# Schematic-Indheater_Altium.net
KiCad netlist of a schematic drawn in Altium Designer
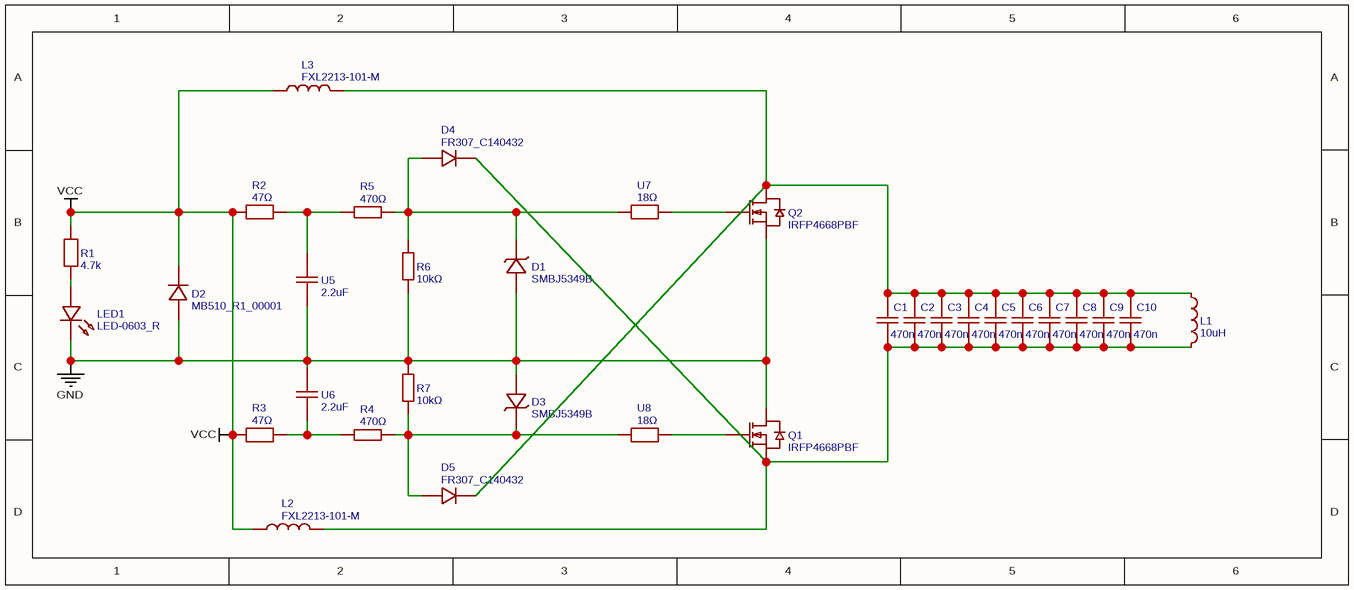
[diagram p0: Schematic-Indheater (Altium).schdoc]

(export (version "E")
  (design (tool "Eeschema 10.0.6"))
  (components
    (comp (ref "C1")
      (value "470n")
      (fields
        (field (name "MANUFACTURER") "faratronic(厦门法拉)")
        (field (name "MANUFACTURER PART") "C222J474K60C000")
        (field (name "CONTRIBUTOR") "LCSC")
      )
      (libsource (lib "altium-import") (part "root_1_470n_"))
    )
    (comp (ref "C2")
      (value "470n")
      (fields
        (field (name "MANUFACTURER") "faratronic(厦门法拉)")
        (field (name "MANUFACTURER PART") "C222J474K60C000")
        (field (name "CONTRIBUTOR") "LCSC")
      )
      (libsource (lib "altium-import") (part "root_1_470n_"))
    )
    (comp (ref "C3")
      (value "470n")
      (fields
        (field (name "MANUFACTURER") "faratronic(厦门法拉)")
        (field (name "MANUFACTURER PART") "C222J474K60C000")
        (field (name "CONTRIBUTOR") "LCSC")
      )
      (libsource (lib "altium-import") (part "root_1_470n_"))
    )
    (comp (ref "C4")
      (value "470n")
      (fields
        (field (name "MANUFACTURER") "faratronic(厦门法拉)")
        (field (name "MANUFACTURER PART") "C222J474K60C000")
        (field (name "CONTRIBUTOR") "LCSC")
      )
      (libsource (lib "altium-import") (part "root_1_470n_"))
    )
    (comp (ref "C5")
      (value "470n")
      (fields
        (field (name "MANUFACTURER") "faratronic(厦门法拉)")
        (field (name "MANUFACTURER PART") "C222J474K60C000")
        (field (name "CONTRIBUTOR") "LCSC")
      )
      (libsource (lib "altium-import") (part "root_1_470n_"))
    )
    (comp (ref "C6")
      (value "470n")
      (fields
        (field (name "MANUFACTURER") "faratronic(厦门法拉)")
        (field (name "MANUFACTURER PART") "C222J474K60C000")
        (field (name "CONTRIBUTOR") "LCSC")
      )
      (libsource (lib "altium-import") (part "root_1_470n_"))
    )
    (comp (ref "C7")
      (value "470n")
      (fields
        (field (name "MANUFACTURER") "faratronic(厦门法拉)")
        (field (name "MANUFACTURER PART") "C222J474K60C000")
        (field (name "CONTRIBUTOR") "LCSC")
      )
      (libsource (lib "altium-import") (part "root_1_470n_"))
    )
    (comp (ref "C8")
      (value "470n")
      (fields
        (field (name "MANUFACTURER") "faratronic(厦门法拉)")
        (field (name "MANUFACTURER PART") "C222J474K60C000")
        (field (name "CONTRIBUTOR") "LCSC")
      )
      (libsource (lib "altium-import") (part "root_1_470n_"))
    )
    (comp (ref "C9")
      (value "470n")
      (fields
        (field (name "MANUFACTURER") "faratronic(厦门法拉)")
        (field (name "MANUFACTURER PART") "C222J474K60C000")
        (field (name "CONTRIBUTOR") "LCSC")
      )
      (libsource (lib "altium-import") (part "root_1_470n_"))
    )
    (comp (ref "C10")
      (value "470n")
      (fields
        (field (name "MANUFACTURER") "faratronic(厦门法拉)")
        (field (name "MANUFACTURER PART") "C222J474K60C000")
        (field (name "CONTRIBUTOR") "LCSC")
      )
      (libsource (lib "altium-import") (part "root_1_470n_"))
    )
    (comp (ref "D1")
      (value "SMBJ5349B")
      (fields (field (name "MANUFACTURER") "LGE(鲁光)") (field (name "CONTRIBUTOR") "LCSC"))
      (libsource (lib "altium-import") (part "root_3_SMBJ5349B_"))
    )
    (comp (ref "D2")
      (value "MB510_R1_00001")
      (fields (field (name "MANUFACTURER") "PANJIT(强茂)") (field (name "CONTRIBUTOR") "LCSC"))
      (libsource (lib "altium-import") (part "root_3_MB510_R1_00001_"))
    )
    (comp (ref "D3")
      (value "SMBJ5349B")
      (fields (field (name "MANUFACTURER") "LGE(鲁光)") (field (name "CONTRIBUTOR") "LCSC"))
      (libsource (lib "altium-import") (part "root_1_SMBJ5349B_"))
    )
    (comp (ref "D4")
      (value "FR307_C140432")
      (fields
        (field (name "MANUFACTURER") "星海")
        (field (name "MANUFACTURER PART") "FR307")
        (field (name "CONTRIBUTOR") "立创EDA官方封装库")
      )
      (libsource (lib "altium-import") (part "root_0_FR307_C140432_"))
    )
    (comp (ref "D5")
      (value "FR307_C140432")
      (fields
        (field (name "MANUFACTURER") "星海")
        (field (name "MANUFACTURER PART") "FR307")
        (field (name "CONTRIBUTOR") "立创EDA官方封装库")
      )
      (libsource (lib "altium-import") (part "root_0_FR307_C140432_"))
    )
    (comp (ref "L1")
      (value "10uH")
      (fields (field (name "CONTRIBUTOR") "LCEDA_Lib"))
      (libsource (lib "altium-import") (part "root_3_10uH_"))
    )
    (comp (ref "L2")
      (value "FXL2213-101-M")
      (fields (field (name "MANUFACTURER") "cjiang") (field (name "CONTRIBUTOR") "mtech"))
      (libsource (lib "altium-import") (part "root_0_FXL2213-101-M_"))
    )
    (comp (ref "L3")
      (value "FXL2213-101-M")
      (fields (field (name "MANUFACTURER") "cjiang") (field (name "CONTRIBUTOR") "mtech"))
      (libsource (lib "altium-import") (part "root_0_FXL2213-101-M_"))
    )
    (comp (ref "LED1")
      (value "LED-0603_R")
      (fields
        (field (name "MANUFACTURER") "EVERLIGHT(台湾亿光)")
        (field (name "MANUFACTURER PART") "19-217/R6C-AL1M2VY/3T")
        (field (name "CONTRIBUTOR") "LCEDA_01")
      )
      (libsource (lib "altium-import") (part "root_3_LED-0603_R_"))
    )
    (comp (ref "Q1")
      (value "IRFP4668PBF")
      (fields (field (name "MANUFACTURER") "Infineon(英飞凌)"))
      (libsource (lib "altium-import") (part "root_0_IRFP4668PBF_"))
    )
    (comp (ref "Q2")
      (value "IRFP4668PBF")
      (fields (field (name "MANUFACTURER") "Infineon(英飞凌)"))
      (libsource (lib "altium-import") (part "root_0_IRFP4668PBF_"))
    )
    (comp (ref "R1")
      (value "4.7k")
      (fields (field (name "CONTRIBUTOR") "LCEDA_Lib"))
      (libsource (lib "altium-import") (part "root_1_4.7k_"))
    )
    (comp (ref "R2")
      (value "47Ω")
      (fields
        (field (name "MANUFACTURER") "TE Connectivity(泰科电子)")
        (field (name "MANUFACTURER PART") "355047RJT")
        (field (name "CONTRIBUTOR") "lcsc")
      )
      (libsource (lib "altium-import") (part "root_0_47Ω_"))
    )
    (comp (ref "R3")
      (value "47Ω")
      (fields
        (field (name "MANUFACTURER") "TE Connectivity(泰科电子)")
        (field (name "MANUFACTURER PART") "355047RJT")
        (field (name "CONTRIBUTOR") "lcsc")
      )
      (libsource (lib "altium-import") (part "root_0_47Ω_"))
    )
    (comp (ref "R4")
      (value "470Ω")
      (fields
        (field (name "MANUFACTURER") "CCO(千志电子)")
        (field (name "MANUFACTURER PART") "CR-M5W470Ω 5% P")
        (field (name "CONTRIBUTOR") "LCSC")
      )
      (libsource (lib "altium-import") (part "root_0_470Ω_"))
    )
    (comp (ref "R5")
      (value "470Ω")
      (fields
        (field (name "MANUFACTURER") "CCO(千志电子)")
        (field (name "MANUFACTURER PART") "CR-M5W470Ω 5% P")
        (field (name "CONTRIBUTOR") "LCSC")
      )
      (libsource (lib "altium-import") (part "root_0_470Ω_"))
    )
    (comp (ref "R6")
      (value "10kΩ")
      (fields
        (field (name "MANUFACTURER") "CCO(千志电子)")
        (field (name "MANUFACTURER PART") "CF1/2W-10KΩ±5% T")
        (field (name "CONTRIBUTOR") "LCSC")
      )
      (libsource (lib "altium-import") (part "root_1_10kΩ_"))
    )
    (comp (ref "R7")
      (value "10kΩ")
      (fields
        (field (name "MANUFACTURER") "CCO(千志电子)")
        (field (name "MANUFACTURER PART") "CF1/2W-10KΩ±5% T")
        (field (name "CONTRIBUTOR") "LCSC")
      )
      (libsource (lib "altium-import") (part "root_1_10kΩ_"))
    )
    (comp (ref "U5")
      (value "2.2uF")
      (fields
        (field (name "MANUFACTURER") "CCTC(三环)")
        (field (name "MANUFACTURER PART") "TCC1206X7R225K101HT")
        (field (name "CONTRIBUTOR") "lcsc")
      )
      (libsource (lib "altium-import") (part "root_1_2.2uF_"))
    )
    (comp (ref "U6")
      (value "2.2uF")
      (fields
        (field (name "MANUFACTURER") "CCTC(三环)")
        (field (name "MANUFACTURER PART") "TCC1206X7R225K101HT")
        (field (name "CONTRIBUTOR") "lcsc")
      )
      (libsource (lib "altium-import") (part "root_1_2.2uF_"))
    )
    (comp (ref "U7")
      (value "18Ω")
      (fields
        (field (name "MANUFACTURER") "FOJAN(富捷)")
        (field (name "MANUFACTURER PART") "FRC0805F18R0TS")
        (field (name "CONTRIBUTOR") "lcsc")
      )
      (libsource (lib "altium-import") (part "root_0_18Ω_"))
    )
    (comp (ref "U8")
      (value "18Ω")
      (fields
        (field (name "MANUFACTURER") "FOJAN(富捷)")
        (field (name "MANUFACTURER PART") "FRC0805F18R0TS")
        (field (name "CONTRIBUTOR") "lcsc")
      )
      (libsource (lib "altium-import") (part "root_0_18Ω_"))
    )
  )
  (nets
    (net (code "1") (name "GND") (class "Default")
      (node (ref "D1") (pin "2") (pinfunction "A_2") (pintype "passive"))
      (node (ref "D2") (pin "2") (pinfunction "A_2") (pintype "passive"))
      (node (ref "D3") (pin "2") (pinfunction "A_2") (pintype "passive"))
      (node (ref "LED1") (pin "2") (pinfunction "2_2") (pintype "passive"))
      (node (ref "Q1") (pin "2") (pinfunction "D_2") (pintype "passive"))
      (node (ref "Q2") (pin "3") (pinfunction "S_3") (pintype "passive"))
      (node (ref "R6") (pin "1") (pinfunction "1_1") (pintype "passive"))
      (node (ref "R7") (pin "2") (pinfunction "2_2") (pintype "passive"))
      (node (ref "U5") (pin "1") (pinfunction "1_1") (pintype "passive"))
      (node (ref "U6") (pin "2") (pinfunction "2_2") (pintype "passive"))
    )
    (net (code "2") (name "Net-(D1-C)") (class "Default")
      (node (ref "D1") (pin "1") (pinfunction "C_1") (pintype "passive"))
      (node (ref "D4") (pin "1") (pinfunction "1_1") (pintype "passive"))
      (node (ref "R5") (pin "2") (pinfunction "2_2") (pintype "passive"))
      (node (ref "R6") (pin "2") (pinfunction "2_2") (pintype "passive"))
      (node (ref "U7") (pin "1") (pinfunction "1_1") (pintype "passive"))
    )
    (net (code "3") (name "Net-(D3-C)") (class "Default")
      (node (ref "D3") (pin "1") (pinfunction "C_1") (pintype "passive"))
      (node (ref "D5") (pin "1") (pinfunction "1_1") (pintype "passive"))
      (node (ref "R4") (pin "2") (pinfunction "2_2") (pintype "passive"))
      (node (ref "R7") (pin "1") (pinfunction "1_1") (pintype "passive"))
      (node (ref "U8") (pin "1") (pinfunction "1_1") (pintype "passive"))
    )
    (net (code "4") (name "Net-(LED1-Pad1)") (class "Default")
      (node (ref "LED1") (pin "1") (pinfunction "1_1") (pintype "passive"))
      (node (ref "R1") (pin "1") (pinfunction "1_1") (pintype "passive"))
    )
    (net (code "5") (name "Net-(Q1-G)") (class "Default")
      (node (ref "Q1") (pin "1") (pinfunction "G_1") (pintype "passive"))
      (node (ref "U8") (pin "2") (pinfunction "2_2") (pintype "passive"))
    )
    (net (code "6") (name "Net-(Q1-S)") (class "Default")
      (node (ref "C1") (pin "1") (pinfunction "1_1") (pintype "passive"))
      (node (ref "C10") (pin "1") (pinfunction "1_1") (pintype "passive"))
      (node (ref "C2") (pin "1") (pinfunction "1_1") (pintype "passive"))
      (node (ref "C3") (pin "1") (pinfunction "1_1") (pintype "passive"))
      (node (ref "C4") (pin "1") (pinfunction "1_1") (pintype "passive"))
      (node (ref "C5") (pin "1") (pinfunction "1_1") (pintype "passive"))
      (node (ref "C6") (pin "1") (pinfunction "1_1") (pintype "passive"))
      (node (ref "C7") (pin "1") (pinfunction "1_1") (pintype "passive"))
      (node (ref "C8") (pin "1") (pinfunction "1_1") (pintype "passive"))
      (node (ref "C9") (pin "1") (pinfunction "1_1") (pintype "passive"))
      (node (ref "D4") (pin "2") (pinfunction "2_2") (pintype "passive"))
      (node (ref "L1") (pin "2") (pinfunction "2_2") (pintype "passive"))
      (node (ref "L2") (pin "2") (pinfunction "2_2") (pintype "passive"))
      (node (ref "Q1") (pin "3") (pinfunction "S_3") (pintype "passive"))
    )
    (net (code "7") (name "Net-(Q2-D)") (class "Default")
      (node (ref "C1") (pin "2") (pinfunction "2_2") (pintype "passive"))
      (node (ref "C10") (pin "2") (pinfunction "2_2") (pintype "passive"))
      (node (ref "C2") (pin "2") (pinfunction "2_2") (pintype "passive"))
      (node (ref "C3") (pin "2") (pinfunction "2_2") (pintype "passive"))
      (node (ref "C4") (pin "2") (pinfunction "2_2") (pintype "passive"))
      (node (ref "C5") (pin "2") (pinfunction "2_2") (pintype "passive"))
      (node (ref "C6") (pin "2") (pinfunction "2_2") (pintype "passive"))
      (node (ref "C7") (pin "2") (pinfunction "2_2") (pintype "passive"))
      (node (ref "C8") (pin "2") (pinfunction "2_2") (pintype "passive"))
      (node (ref "C9") (pin "2") (pinfunction "2_2") (pintype "passive"))
      (node (ref "D5") (pin "2") (pinfunction "2_2") (pintype "passive"))
      (node (ref "L1") (pin "1") (pinfunction "1_1") (pintype "passive"))
      (node (ref "L3") (pin "2") (pinfunction "2_2") (pintype "passive"))
      (node (ref "Q2") (pin "2") (pinfunction "D_2") (pintype "passive"))
    )
    (net (code "8") (name "Net-(Q2-G)") (class "Default")
      (node (ref "Q2") (pin "1") (pinfunction "G_1") (pintype "passive"))
      (node (ref "U7") (pin "2") (pinfunction "2_2") (pintype "passive"))
    )
    (net (code "9") (name "Net-(R2-Pad2)") (class "Default")
      (node (ref "R2") (pin "2") (pinfunction "2_2") (pintype "passive"))
      (node (ref "R5") (pin "1") (pinfunction "1_1") (pintype "passive"))
      (node (ref "U5") (pin "2") (pinfunction "2_2") (pintype "passive"))
    )
    (net (code "10") (name "Net-(R3-Pad2)") (class "Default")
      (node (ref "R3") (pin "2") (pinfunction "2_2") (pintype "passive"))
      (node (ref "R4") (pin "1") (pinfunction "1_1") (pintype "passive"))
      (node (ref "U6") (pin "1") (pinfunction "1_1") (pintype "passive"))
    )
    (net (code "11") (name "VCC") (class "Default")
      (node (ref "D2") (pin "1") (pinfunction "K_1") (pintype "passive"))
      (node (ref "L2") (pin "1") (pinfunction "1_1") (pintype "passive"))
      (node (ref "L3") (pin "1") (pinfunction "1_1") (pintype "passive"))
      (node (ref "R1") (pin "2") (pinfunction "2_2") (pintype "passive"))
      (node (ref "R2") (pin "1") (pinfunction "1_1") (pintype "passive"))
      (node (ref "R3") (pin "1") (pinfunction "1_1") (pintype "passive"))
    )
  )
)
